# Input.net
KiCad netlist of a schematic drawn in Altium Designer
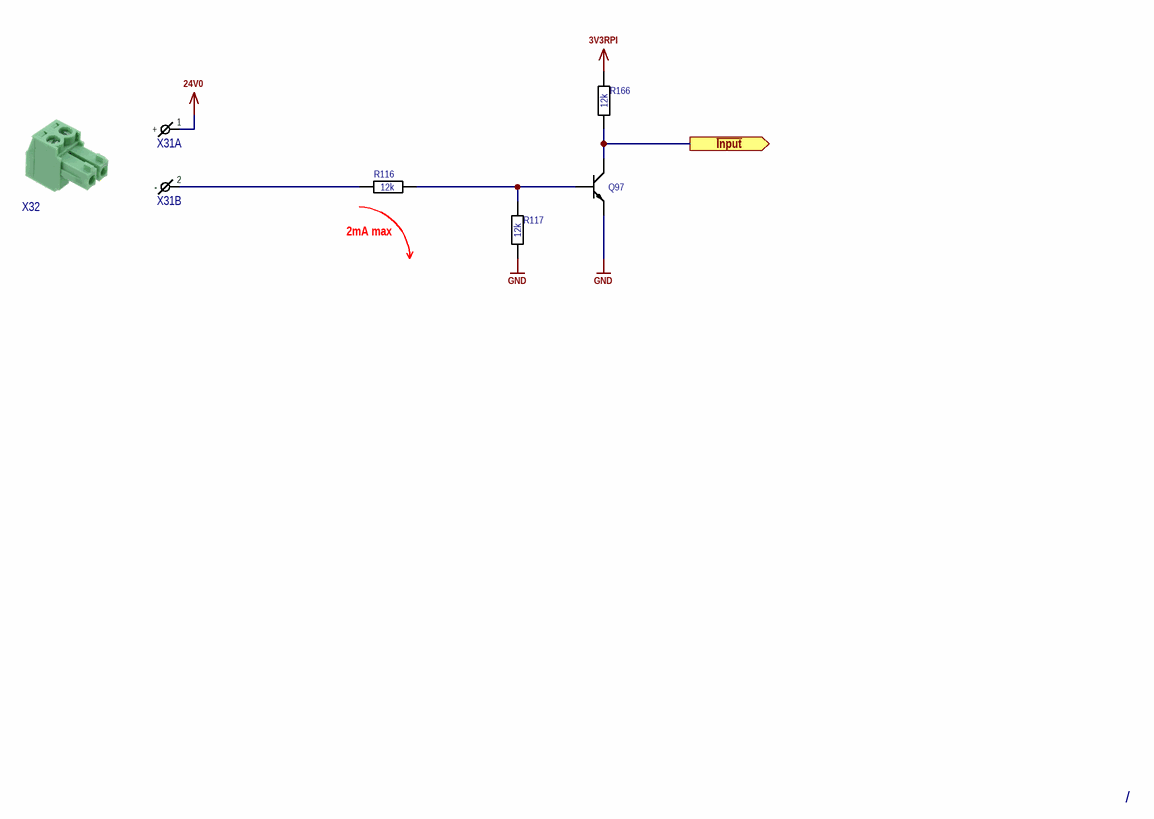
[diagram p0: Input.SchDoc]

(export (version "E")
  (design (tool "Eeschema 10.0.6"))
  (components
    (comp (ref "Q97")
      (value "Q")
      (footprint "SOT23-3")
      (description "MOSFET N-CH 25V 680MA SOT-23")
      (fields
        (field (name "02. DISTRIBUTOR PART NUMBER") "FDV303NDKR-ND")
        (field (name "07. MANUFACTURER  PART NUMBER") "FDV303N")
        (field (name "13. CREATED DATE/NAME") "AUG 2018 / Hören")
      )
      (libsource (lib "PCB-Tester-Board-V1") (part "NPN"))
    )
    (comp (ref "R116")
      (value "12k")
      (footprint "R1206 Reflow")
      (description "RES SMD 12K OHM 1% 1/4W 1206")
      (fields
        (field (name "TOLERANCE") "±1%")
        (field (name "02. DISTRIBUTOR PART NUMBER") "311-12.0KFRTR-ND")
      )
      (libsource (lib "") (part "R_23_1"))
    )
    (comp (ref "R117")
      (value "12k")
      (footprint "R1206 Reflow")
      (description "RES SMD 12K OHM 1% 1/4W 1206")
      (fields
        (field (name "TOLERANCE") "±1%")
        (field (name "02. DISTRIBUTOR PART NUMBER") "311-12.0KFRTR-ND")
      )
      (libsource (lib "PCB-Tester-Board-V1") (part "R_23"))
    )
    (comp (ref "R166")
      (value "12k")
      (footprint "R1206 Reflow")
      (description "RES SMD 12K OHM 1% 1/4W 1206")
      (fields
        (field (name "TOLERANCE") "±1%")
        (field (name "02. DISTRIBUTOR PART NUMBER") "311-12.0KFRTR-ND")
      )
      (libsource (lib "PCB-Tester-Board-V1") (part "R_23"))
    )
    (comp (ref "X31")
      (value "X")
      (footprint "691322310002")
      (description "TERM BLOCK HDR 2POS 90DEG 3.81MM")
      (fields
        (field (name "02. DISTRIBUTOR PART NUMBER") "732-2088-ND")
        (field (name "07. MANUFACTURER  PART NUMBER") "691322310002")
        (field (name "13. CREATED DATE/NAME") "??? / Hören")
      )
      (libsource (lib "Connectors") (part "691322310002"))
    )
    (comp (ref "X32")
      (value "X")
      (footprint "691361300002")
      (description "TERM BLOCK PLUG 2POS STR 3.81MM")
      (fields
        (field (name "02. DISTRIBUTOR PART NUMBER") "732-2076-ND")
        (field (name "07. MANUFACTURER  PART NUMBER") "691361300002")
        (field (name "13. CREATED DATE/NAME") "??? / Hören")
      )
      (libsource (lib "PCB-Tester-Board-V1") (part "691361300002"))
    )
  )
  (nets
    (net (code "1") (name "/~{Input}") (class "Default")
      (node (ref "Q97") (pin "3") (pinfunction "C_3") (pintype "passive"))
      (node (ref "R166") (pin "1") (pinfunction "1_1") (pintype "passive"))
    )
    (net (code "2") (name "3V3RPI") (class "Default")
      (node (ref "R166") (pin "2") (pinfunction "2_2") (pintype "passive"))
    )
    (net (code "3") (name "24V0") (class "Default")
      (node (ref "X31") (pin "1") (pinfunction "+_1") (pintype "passive"))
    )
    (net (code "4") (name "GND") (class "Default")
      (node (ref "Q97") (pin "2") (pinfunction "E_2") (pintype "passive"))
      (node (ref "R117") (pin "1") (pinfunction "1_1") (pintype "passive"))
    )
    (net (code "5") (name "Net-(Q97-B)") (class "Default")
      (node (ref "Q97") (pin "1") (pinfunction "B_1") (pintype "passive"))
      (node (ref "R116") (pin "2") (pinfunction "2_2") (pintype "passive"))
      (node (ref "R117") (pin "2") (pinfunction "2_2") (pintype "passive"))
    )
    (net (code "6") (name "Net-(X31B--)") (class "Default")
      (node (ref "R116") (pin "1") (pinfunction "1_1") (pintype "passive"))
      (node (ref "X31") (pin "2") (pinfunction "-_2") (pintype "passive"))
    )
  )
)
